# Mbed.net
KiCad netlist of a schematic drawn in Altium Designer
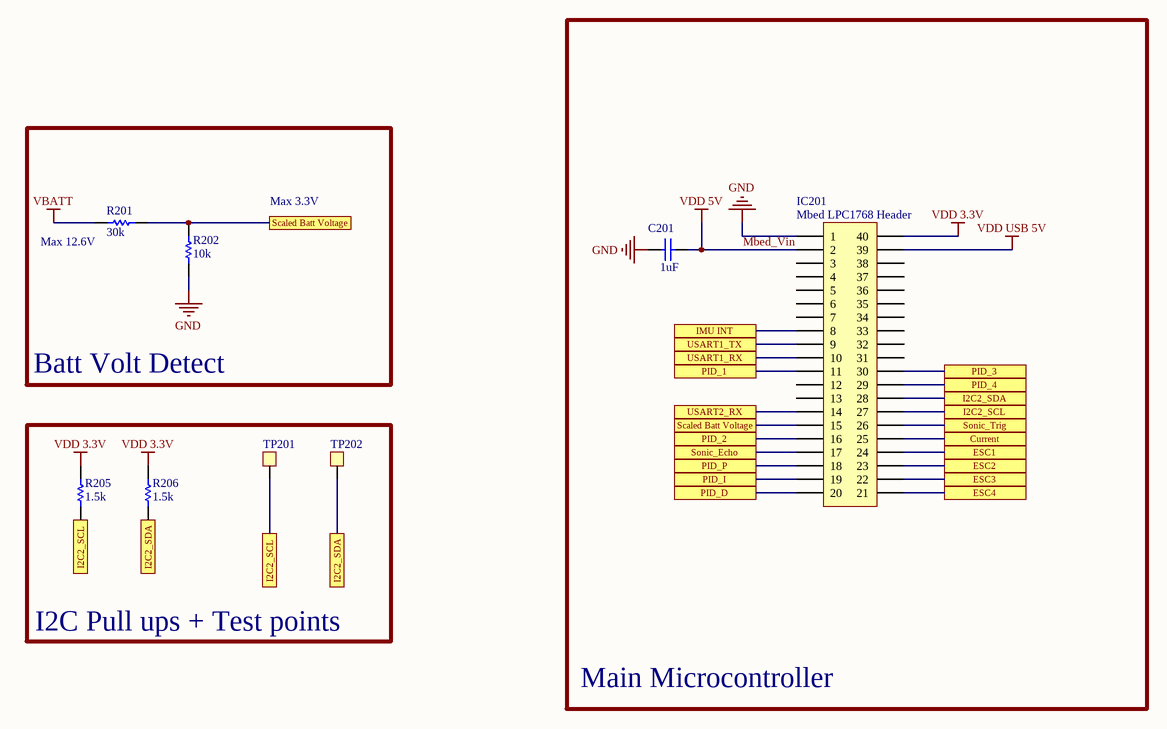
[diagram p0: Mbed.SchDoc]

(export (version "E")
  (design (tool "Eeschema 10.0.6"))
  (components
    (comp (ref "C201")
      (value "1uF")
      (footprint "0805 Cap")
      (description "Capacitor Box")
      (fields (field (name "Comment") "0805") (field (name "PUBLISHER") "Altium Limited"))
      (libsource (lib "Miscellaneous Devices") (part "Cap"))
    )
    (comp (ref "IC201")
      (value "Mbed LPC1768 Header")
      (footprint "Mbed LPC1768")
      (fields (field (name "PUBLISHER") "Altium Limited"))
      (libsource (lib "Miscellaneous Connectors") (part "Header 20X2"))
    )
    (comp (ref "R201")
      (value "30k")
      (footprint "0603")
      (description "Resistor")
      (fields (field (name "Comment") "0603") (field (name "PUBLISHER") "Altium Limited"))
      (libsource (lib "Miscellaneous Devices") (part "Res1"))
    )
    (comp (ref "R202")
      (value "10k")
      (footprint "0603")
      (description "Resistor")
      (fields (field (name "Comment") "0603") (field (name "PUBLISHER") "Altium Limited"))
      (libsource (lib "Miscellaneous Devices") (part "Res1"))
    )
    (comp (ref "R205")
      (value "1.5k")
      (footprint "0603")
      (description "Resistor")
      (fields (field (name "Comment") "0603") (field (name "PUBLISHER") "Altium Limited"))
      (libsource (lib "Miscellaneous Devices") (part "Res1"))
    )
    (comp (ref "R206")
      (value "1.5k")
      (footprint "0603")
      (description "Resistor")
      (fields (field (name "Comment") "0603") (field (name "PUBLISHER") "Altium Limited"))
      (libsource (lib "Miscellaneous Devices") (part "Res1"))
    )
    (comp (ref "TP201")
      (value "Test Point")
      (footprint "Test Point THT 1mm")
      (libsource (lib "FYP_Drone") (part "Test Point"))
    )
    (comp (ref "TP202")
      (value "Test Point")
      (footprint "Test Point THT 1mm")
      (libsource (lib "FYP_Drone") (part "Test Point"))
    )
  )
  (nets
    (net (code "1") (name "/Current") (class "Default")
      (node (ref "IC201") (pin "25") (pinfunction "25_25") (pintype "passive"))
    )
    (net (code "2") (name "/ESC1") (class "Default")
      (node (ref "IC201") (pin "24") (pinfunction "24_24") (pintype "passive"))
    )
    (net (code "3") (name "/ESC2") (class "Default")
      (node (ref "IC201") (pin "23") (pinfunction "23_23") (pintype "passive"))
    )
    (net (code "4") (name "/ESC3") (class "Default")
      (node (ref "IC201") (pin "22") (pinfunction "22_22") (pintype "passive"))
    )
    (net (code "5") (name "/ESC4") (class "Default")
      (node (ref "IC201") (pin "21") (pinfunction "21_21") (pintype "passive"))
    )
    (net (code "6") (name "/I2C2_SCL") (class "Default")
      (node (ref "IC201") (pin "27") (pinfunction "27_27") (pintype "passive"))
      (node (ref "R205") (pin "2") (pinfunction "2_2") (pintype "passive"))
      (node (ref "TP201") (pin "1") (pintype "passive"))
    )
    (net (code "7") (name "/I2C2_SDA") (class "Default")
      (node (ref "IC201") (pin "28") (pinfunction "28_28") (pintype "passive"))
      (node (ref "R206") (pin "2") (pinfunction "2_2") (pintype "passive"))
      (node (ref "TP202") (pin "1") (pintype "passive"))
    )
    (net (code "8") (name "/IMU INT") (class "Default")
      (node (ref "IC201") (pin "8") (pinfunction "8_8") (pintype "passive"))
    )
    (net (code "9") (name "/PID_1") (class "Default")
      (node (ref "IC201") (pin "11") (pinfunction "11_11") (pintype "passive"))
    )
    (net (code "10") (name "/PID_2") (class "Default")
      (node (ref "IC201") (pin "16") (pinfunction "16_16") (pintype "passive"))
    )
    (net (code "11") (name "/PID_3") (class "Default")
      (node (ref "IC201") (pin "30") (pinfunction "30_30") (pintype "passive"))
    )
    (net (code "12") (name "/PID_4") (class "Default")
      (node (ref "IC201") (pin "29") (pinfunction "29_29") (pintype "passive"))
    )
    (net (code "13") (name "/PID_D") (class "Default")
      (node (ref "IC201") (pin "20") (pinfunction "20_20") (pintype "passive"))
    )
    (net (code "14") (name "/PID_I") (class "Default")
      (node (ref "IC201") (pin "19") (pinfunction "19_19") (pintype "passive"))
    )
    (net (code "15") (name "/PID_P") (class "Default")
      (node (ref "IC201") (pin "18") (pinfunction "18_18") (pintype "passive"))
    )
    (net (code "16") (name "/Scaled Batt Voltage") (class "Default")
      (node (ref "IC201") (pin "15") (pinfunction "15_15") (pintype "passive"))
      (node (ref "R201") (pin "2") (pinfunction "2_2") (pintype "passive"))
      (node (ref "R202") (pin "1") (pinfunction "1_1") (pintype "passive"))
    )
    (net (code "17") (name "/Sonic_Echo") (class "Default")
      (node (ref "IC201") (pin "17") (pinfunction "17_17") (pintype "passive"))
    )
    (net (code "18") (name "/Sonic_Trig") (class "Default")
      (node (ref "IC201") (pin "26") (pinfunction "26_26") (pintype "passive"))
    )
    (net (code "19") (name "/USART1_RX") (class "Default")
      (node (ref "IC201") (pin "10") (pinfunction "10_10") (pintype "passive"))
    )
    (net (code "20") (name "/USART1_TX") (class "Default")
      (node (ref "IC201") (pin "9") (pinfunction "9_9") (pintype "passive"))
    )
    (net (code "21") (name "/USART2_RX") (class "Default")
      (node (ref "IC201") (pin "14") (pinfunction "14_14") (pintype "passive"))
    )
    (net (code "22") (name "GND") (class "Default")
      (node (ref "C201") (pin "2") (pinfunction "2_2") (pintype "passive"))
      (node (ref "IC201") (pin "1") (pinfunction "1_1") (pintype "passive"))
      (node (ref "R202") (pin "2") (pinfunction "2_2") (pintype "passive"))
    )
    (net (code "23") (name "VBATT") (class "Default")
      (node (ref "R201") (pin "1") (pinfunction "1_1") (pintype "passive"))
    )
    (net (code "24") (name "VDD 3.3V") (class "Default")
      (node (ref "IC201") (pin "40") (pinfunction "40_40") (pintype "passive"))
      (node (ref "R205") (pin "1") (pinfunction "1_1") (pintype "passive"))
      (node (ref "R206") (pin "1") (pinfunction "1_1") (pintype "passive"))
    )
    (net (code "25") (name "VDD 5V") (class "Default")
      (node (ref "C201") (pin "1") (pinfunction "1_1") (pintype "passive"))
      (node (ref "IC201") (pin "2") (pinfunction "2_2") (pintype "passive"))
    )
    (net (code "26") (name "VDD USB 5V") (class "Default")
      (node (ref "IC201") (pin "39") (pinfunction "39_39") (pintype "passive"))
    )
    (net (code "27") (name "unconnected-(IC201-Pad3)") (class "Default")
      (node (ref "IC201") (pin "3") (pinfunction "3_3") (pintype "passive"))
    )
    (net (code "28") (name "unconnected-(IC201-Pad4)") (class "Default")
      (node (ref "IC201") (pin "4") (pinfunction "4_4") (pintype "passive"))
    )
    (net (code "29") (name "unconnected-(IC201-Pad5)") (class "Default")
      (node (ref "IC201") (pin "5") (pinfunction "5_5") (pintype "passive"))
    )
    (net (code "30") (name "unconnected-(IC201-Pad6)") (class "Default")
      (node (ref "IC201") (pin "6") (pinfunction "6_6") (pintype "passive"))
    )
    (net (code "31") (name "unconnected-(IC201-Pad7)") (class "Default")
      (node (ref "IC201") (pin "7") (pinfunction "7_7") (pintype "passive"))
    )
    (net (code "32") (name "unconnected-(IC201-Pad12)") (class "Default")
      (node (ref "IC201") (pin "12") (pinfunction "12_12") (pintype "passive"))
    )
    (net (code "33") (name "unconnected-(IC201-Pad13)") (class "Default")
      (node (ref "IC201") (pin "13") (pinfunction "13_13") (pintype "passive"))
    )
    (net (code "34") (name "unconnected-(IC201-Pad31)") (class "Default")
      (node (ref "IC201") (pin "31") (pinfunction "31_31") (pintype "passive"))
    )
    (net (code "35") (name "unconnected-(IC201-Pad32)") (class "Default")
      (node (ref "IC201") (pin "32") (pinfunction "32_32") (pintype "passive"))
    )
    (net (code "36") (name "unconnected-(IC201-Pad33)") (class "Default")
      (node (ref "IC201") (pin "33") (pinfunction "33_33") (pintype "passive"))
    )
    (net (code "37") (name "unconnected-(IC201-Pad34)") (class "Default")
      (node (ref "IC201") (pin "34") (pinfunction "34_34") (pintype "passive"))
    )
    (net (code "38") (name "unconnected-(IC201-Pad35)") (class "Default")
      (node (ref "IC201") (pin "35") (pinfunction "35_35") (pintype "passive"))
    )
    (net (code "39") (name "unconnected-(IC201-Pad36)") (class "Default")
      (node (ref "IC201") (pin "36") (pinfunction "36_36") (pintype "passive"))
    )
    (net (code "40") (name "unconnected-(IC201-Pad37)") (class "Default")
      (node (ref "IC201") (pin "37") (pinfunction "37_37") (pintype "passive"))
    )
    (net (code "41") (name "unconnected-(IC201-Pad38)") (class "Default")
      (node (ref "IC201") (pin "38") (pinfunction "38_38") (pintype "passive"))
    )
  )
)
